# Bee_Snuggler_-_Devel.net
KiCad netlist of a schematic drawn in EAGLE
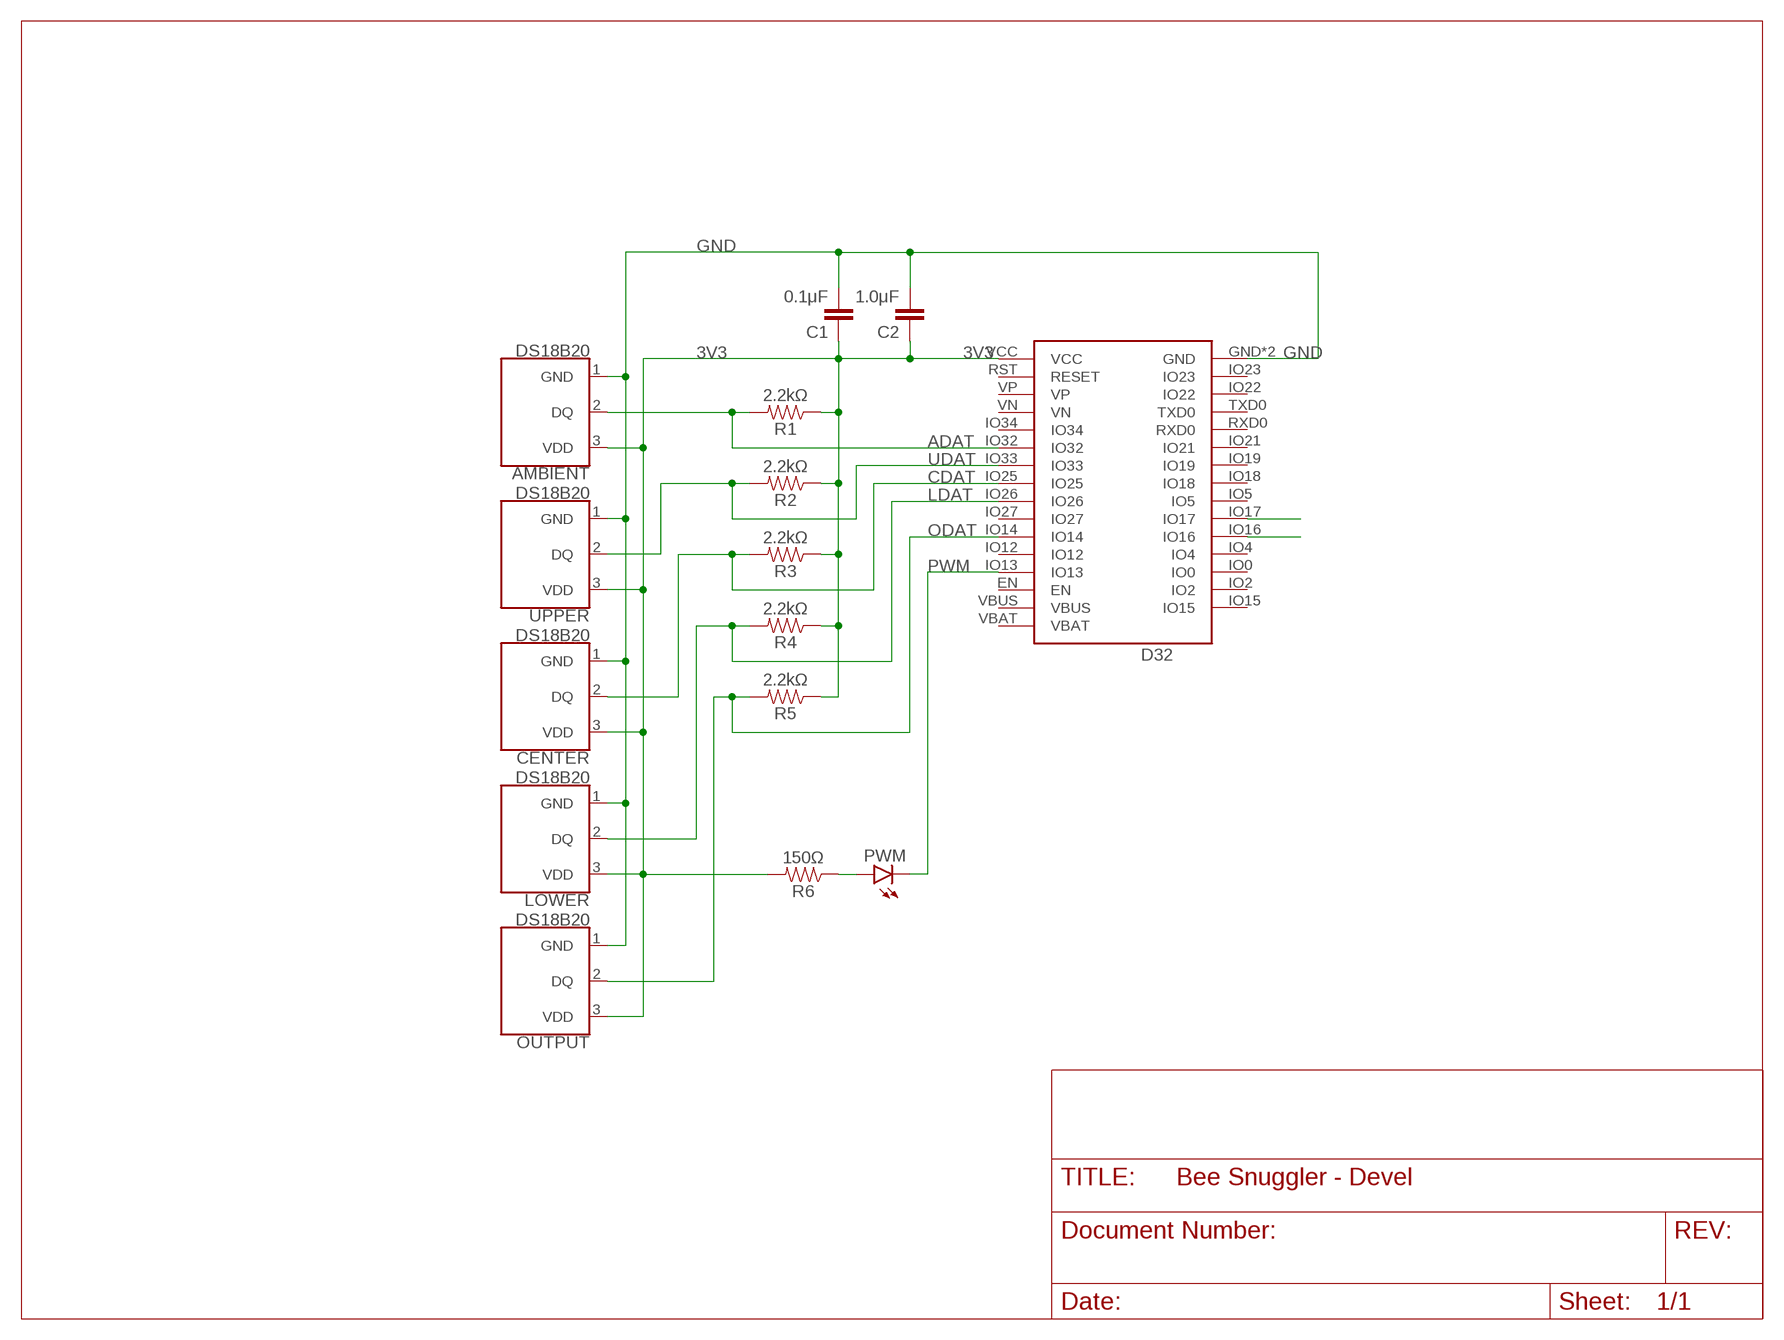
[diagram p0: schematic, sheet 1]

(export (version "E")
  (design (tool "Eeschema 10.0.6"))
  (components
    (comp (ref "AMBIENT")
      (value "DS18B20")
      (footprint "eagle-import:TO-92-AMMO")
      (libsource (lib "eagle-import") (part "DS18B20"))
    )
    (comp (ref "C1")
      (value "0.1μF")
      (footprint "eagle-import:CAP_PTH-2.54")
      (libsource (lib "eagle-import") (part "CAP_CERAMIC_2.54"))
    )
    (comp (ref "C2")
      (value "1.0μF")
      (footprint "eagle-import:CAP_PTH-2.54")
      (libsource (lib "eagle-import") (part "CAP_CERAMIC_2.54"))
    )
    (comp (ref "CENTER")
      (value "DS18B20")
      (footprint "eagle-import:TO-92-AMMO")
      (libsource (lib "eagle-import") (part "DS18B20"))
    )
    (comp (ref "D32")
      (value "Lolin D32")
      (footprint "eagle-import:D32_PRO")
      (libsource (lib "eagle-import") (part "WEMOS-D32D32_PRO"))
    )
    (comp (ref "LOWER")
      (value "DS18B20")
      (footprint "eagle-import:TO-92-AMMO")
      (libsource (lib "eagle-import") (part "DS18B20"))
    )
    (comp (ref "OUTPUT")
      (value "DS18B20")
      (footprint "eagle-import:TO-92-AMMO")
      (libsource (lib "eagle-import") (part "DS18B20"))
    )
    (comp (ref "PWM")
      (value "LED5MM")
      (footprint "eagle-import:LED5MM")
      (libsource (lib "eagle-import") (part "LED5MM"))
    )
    (comp (ref "R1")
      (value "2.2kΩ")
      (footprint "eagle-import:AXIAL-0.3")
      (libsource (lib "eagle-import") (part "RESISTORAXIAL-0.3"))
    )
    (comp (ref "R2")
      (value "2.2kΩ")
      (footprint "eagle-import:AXIAL-0.3")
      (libsource (lib "eagle-import") (part "RESISTORAXIAL-0.3"))
    )
    (comp (ref "R3")
      (value "2.2kΩ")
      (footprint "eagle-import:AXIAL-0.3")
      (libsource (lib "eagle-import") (part "RESISTORAXIAL-0.3"))
    )
    (comp (ref "R4")
      (value "2.2kΩ")
      (footprint "eagle-import:AXIAL-0.3")
      (libsource (lib "eagle-import") (part "RESISTORAXIAL-0.3"))
    )
    (comp (ref "R5")
      (value "2.2kΩ")
      (footprint "eagle-import:AXIAL-0.3")
      (libsource (lib "eagle-import") (part "RESISTORAXIAL-0.3"))
    )
    (comp (ref "R6")
      (value "150Ω")
      (footprint "eagle-import:AXIAL-0.3")
      (libsource (lib "eagle-import") (part "RESISTORAXIAL-0.3"))
    )
    (comp (ref "UPPER")
      (value "DS18B20")
      (footprint "eagle-import:TO-92-AMMO")
      (libsource (lib "eagle-import") (part "DS18B20"))
    )
  )
  (nets
    (net (code "1") (name "/3V3") (class "Default")
      (node (ref "AMBIENT") (pin "3") (pinfunction "VDD_3") (pintype "power_in"))
      (node (ref "C1") (pin "1") (pinfunction "1_1") (pintype "passive"))
      (node (ref "C2") (pin "1") (pinfunction "1_1") (pintype "passive"))
      (node (ref "CENTER") (pin "3") (pinfunction "VDD_3") (pintype "power_in"))
      (node (ref "D32") (pin "VCC") (pinfunction "VCC_VCC") (pintype "power_in"))
      (node (ref "LOWER") (pin "3") (pinfunction "VDD_3") (pintype "power_in"))
      (node (ref "OUTPUT") (pin "3") (pinfunction "VDD_3") (pintype "power_in"))
      (node (ref "R1") (pin "P$1") (pinfunction "1_P$1") (pintype "passive"))
      (node (ref "R2") (pin "P$1") (pinfunction "1_P$1") (pintype "passive"))
      (node (ref "R3") (pin "P$1") (pinfunction "1_P$1") (pintype "passive"))
      (node (ref "R4") (pin "P$1") (pinfunction "1_P$1") (pintype "passive"))
      (node (ref "R5") (pin "P$1") (pinfunction "1_P$1") (pintype "passive"))
      (node (ref "R6") (pin "P$2") (pinfunction "2_P$2") (pintype "passive"))
      (node (ref "UPPER") (pin "3") (pinfunction "VDD_3") (pintype "power_in"))
    )
    (net (code "2") (name "/ADAT") (class "Default")
      (node (ref "AMBIENT") (pin "2") (pinfunction "DQ_2") (pintype "bidirectional"))
      (node (ref "D32") (pin "IO32") (pinfunction "IO32_IO32") (pintype "bidirectional"))
      (node (ref "R1") (pin "P$2") (pinfunction "2_P$2") (pintype "passive"))
    )
    (net (code "3") (name "/CDAT") (class "Default")
      (node (ref "CENTER") (pin "2") (pinfunction "DQ_2") (pintype "bidirectional"))
      (node (ref "D32") (pin "IO25") (pinfunction "IO25_IO25") (pintype "bidirectional"))
      (node (ref "R3") (pin "P$2") (pinfunction "2_P$2") (pintype "passive"))
    )
    (net (code "4") (name "/GND") (class "Default")
      (node (ref "AMBIENT") (pin "1") (pinfunction "GND_1") (pintype "power_in"))
      (node (ref "C1") (pin "2") (pinfunction "2_2") (pintype "passive"))
      (node (ref "C2") (pin "2") (pinfunction "2_2") (pintype "passive"))
      (node (ref "CENTER") (pin "1") (pinfunction "GND_1") (pintype "power_in"))
      (node (ref "D32") (pin "GND") (pinfunction "GND_GND") (pintype "power_in"))
      (node (ref "D32") (pin "GND2") (pinfunction "GND_GND2") (pintype "power_in"))
      (node (ref "LOWER") (pin "1") (pinfunction "GND_1") (pintype "power_in"))
      (node (ref "OUTPUT") (pin "1") (pinfunction "GND_1") (pintype "power_in"))
      (node (ref "UPPER") (pin "1") (pinfunction "GND_1") (pintype "power_in"))
    )
    (net (code "5") (name "/LDAT") (class "Default")
      (node (ref "D32") (pin "IO26") (pinfunction "IO26_IO26") (pintype "bidirectional"))
      (node (ref "LOWER") (pin "2") (pinfunction "DQ_2") (pintype "bidirectional"))
      (node (ref "R4") (pin "P$2") (pinfunction "2_P$2") (pintype "passive"))
    )
    (net (code "6") (name "/ODAT") (class "Default")
      (node (ref "D32") (pin "IO14") (pinfunction "IO14_IO14") (pintype "bidirectional"))
      (node (ref "OUTPUT") (pin "2") (pinfunction "DQ_2") (pintype "bidirectional"))
      (node (ref "R5") (pin "P$2") (pinfunction "2_P$2") (pintype "passive"))
    )
    (net (code "7") (name "/PWM") (class "Default")
      (node (ref "D32") (pin "IO13") (pinfunction "IO13_IO13") (pintype "bidirectional"))
      (node (ref "PWM") (pin "K") (pinfunction "C_K") (pintype "passive"))
    )
    (net (code "8") (name "/UDAT") (class "Default")
      (node (ref "D32") (pin "IO33") (pinfunction "IO33_IO33") (pintype "bidirectional"))
      (node (ref "R2") (pin "P$2") (pinfunction "2_P$2") (pintype "passive"))
      (node (ref "UPPER") (pin "2") (pinfunction "DQ_2") (pintype "bidirectional"))
    )
    (net (code "9") (name "Net-(R6-1)") (class "Default")
      (node (ref "PWM") (pin "A") (pinfunction "A_A") (pintype "passive"))
      (node (ref "R6") (pin "P$1") (pinfunction "1_P$1") (pintype "passive"))
    )
    (net (code "10") (name "unconnected-(D32-PadEN)") (class "Default")
      (node (ref "D32") (pin "EN") (pinfunction "EN_EN") (pintype "bidirectional"))
    )
    (net (code "11") (name "unconnected-(D32-PadIO0)") (class "Default")
      (node (ref "D32") (pin "IO0") (pinfunction "IO0_IO0") (pintype "bidirectional"))
    )
    (net (code "12") (name "unconnected-(D32-PadIO2)") (class "Default")
      (node (ref "D32") (pin "IO2") (pinfunction "IO2_IO2") (pintype "bidirectional"))
    )
    (net (code "13") (name "unconnected-(D32-PadIO4)") (class "Default")
      (node (ref "D32") (pin "IO4") (pinfunction "IO4_IO4") (pintype "bidirectional"))
    )
    (net (code "14") (name "unconnected-(D32-PadIO5)") (class "Default")
      (node (ref "D32") (pin "IO5") (pinfunction "IO5_IO5") (pintype "bidirectional"))
    )
    (net (code "15") (name "unconnected-(D32-PadIO12)") (class "Default")
      (node (ref "D32") (pin "IO12") (pinfunction "IO12_IO12") (pintype "bidirectional"))
    )
    (net (code "16") (name "unconnected-(D32-PadIO15)") (class "Default")
      (node (ref "D32") (pin "IO15") (pinfunction "IO15_IO15") (pintype "bidirectional"))
    )
    (net (code "17") (name "unconnected-(D32-PadIO16)") (class "Default")
      (node (ref "D32") (pin "IO16") (pinfunction "IO16_IO16") (pintype "bidirectional"))
    )
    (net (code "18") (name "unconnected-(D32-PadIO17)") (class "Default")
      (node (ref "D32") (pin "IO17") (pinfunction "IO17_IO17") (pintype "bidirectional"))
    )
    (net (code "19") (name "unconnected-(D32-PadIO18)") (class "Default")
      (node (ref "D32") (pin "IO18") (pinfunction "IO18_IO18") (pintype "bidirectional"))
    )
    (net (code "20") (name "unconnected-(D32-PadIO19)") (class "Default")
      (node (ref "D32") (pin "IO19") (pinfunction "IO19_IO19") (pintype "bidirectional"))
    )
    (net (code "21") (name "unconnected-(D32-PadIO21)") (class "Default")
      (node (ref "D32") (pin "IO21") (pinfunction "IO21_IO21") (pintype "bidirectional"))
    )
    (net (code "22") (name "unconnected-(D32-PadIO22)") (class "Default")
      (node (ref "D32") (pin "IO22") (pinfunction "IO22_IO22") (pintype "bidirectional"))
    )
    (net (code "23") (name "unconnected-(D32-PadIO23)") (class "Default")
      (node (ref "D32") (pin "IO23") (pinfunction "IO23_IO23") (pintype "bidirectional"))
    )
    (net (code "24") (name "unconnected-(D32-PadIO27)") (class "Default")
      (node (ref "D32") (pin "IO27") (pinfunction "IO27_IO27") (pintype "bidirectional"))
    )
    (net (code "25") (name "unconnected-(D32-PadIO34)") (class "Default")
      (node (ref "D32") (pin "IO34") (pinfunction "IO34_IO34") (pintype "bidirectional"))
    )
    (net (code "26") (name "unconnected-(D32-PadRXD0)") (class "Default")
      (node (ref "D32") (pin "RXD0") (pinfunction "RXD0_RXD0") (pintype "input"))
    )
    (net (code "27") (name "unconnected-(D32-PadTXD0)") (class "Default")
      (node (ref "D32") (pin "TXD0") (pinfunction "TXD0_TXD0") (pintype "output"))
    )
    (net (code "28") (name "unconnected-(D32-PadVBAT)") (class "Default")
      (node (ref "D32") (pin "VBAT") (pinfunction "VBAT_VBAT") (pintype "bidirectional"))
    )
    (net (code "29") (name "unconnected-(D32-PadVBUS)") (class "Default")
      (node (ref "D32") (pin "VBUS") (pinfunction "VBUS_VBUS") (pintype "bidirectional"))
    )
    (net (code "30") (name "unconnected-(D32-PadVN)") (class "Default")
      (node (ref "D32") (pin "VN") (pinfunction "VN_VN") (pintype "bidirectional"))
    )
    (net (code "31") (name "unconnected-(D32-PadVP)") (class "Default")
      (node (ref "D32") (pin "VP") (pinfunction "VP_VP") (pintype "bidirectional"))
    )
    (net (code "32") (name "unconnected-(D32-RESET-PadRST)") (class "Default")
      (node (ref "D32") (pin "RST") (pinfunction "RESET_RST") (pintype "bidirectional"))
    )
  )
)
